# design.net
KiCad netlist of a schematic drawn in Altium Designer
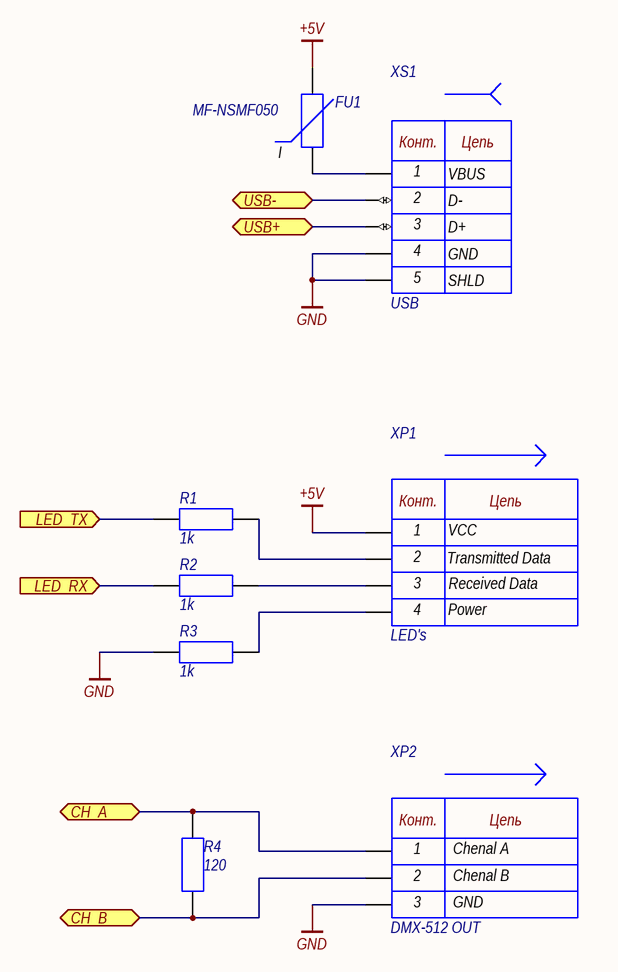
[diagram p0: Коммутация.SchDoc]

(export (version "E")
  (design (tool "Eeschema 10.0.6"))
  (components
    (comp (ref "FU1")
      (value "MF-NSMF050")
      (footprint "Components:F1206 Style1")
      (description "13.2V 0.5A")
      (fields (field (name "Comment") "MF-NSMF050_V"))
      (libsource (lib "Предохранители") (part "MF-NSMF050_V"))
    )
    (comp (ref "R1")
      (value "1k")
      (footprint "Components:R1206")
      (fields (field (name "Comment") "Res 1k"))
      (libsource (lib "") (part "Res 1k_1"))
    )
    (comp (ref "R2")
      (value "1k")
      (footprint "Components:R1206")
      (fields (field (name "Comment") "Res 1k"))
      (libsource (lib "") (part "Res 1k_1"))
    )
    (comp (ref "R3")
      (value "1k")
      (footprint "Components:R1206")
      (fields (field (name "Comment") "Res 1k"))
      (libsource (lib "Резисторы") (part "Res 1k"))
    )
    (comp (ref "R4")
      (value "120")
      (footprint "Components:R1206")
      (fields (field (name "Comment") "Res 120"))
      (libsource (lib "Резисторы") (part "Res 120"))
    )
    (comp (ref "XP1")
      (value "LED's")
      (footprint "Components:WF-4 (DS1070-4M)")
      (description "Power Con (DS1070-4M)")
      (fields (field (name "Comment") "WF-4"))
      (libsource (lib "Разъемы") (part "WF-4"))
    )
    (comp (ref "XP2")
      (value "DMX-512 OUT")
      (footprint "Components:WF-3")
      (description "Power Con (DS1070-4M)")
      (fields (field (name "Comment") "WF-3"))
      (libsource (lib "Разъемы") (part "WF-3"))
    )
    (comp (ref "XS1")
      (value "USB")
      (footprint "Components:USB-B")
      (description "Female B")
      (fields (field (name "Comment") "USB B"))
      (libsource (lib "Разъемы") (part "USB B"))
    )
  )
  (nets
    (net (code "1") (name "+5V") (class "Default")
      (node (ref "FU1") (pin "2") (pinfunction "2_2") (pintype "passive"))
      (node (ref "XP1") (pin "1") (pinfunction "1_1") (pintype "passive"))
    )
    (net (code "2") (name "/CH_A") (class "Default")
      (node (ref "R4") (pin "2") (pinfunction "2_2") (pintype "passive"))
      (node (ref "XP2") (pin "1") (pinfunction "1_1") (pintype "passive"))
    )
    (net (code "3") (name "/CH_B") (class "Default")
      (node (ref "R4") (pin "1") (pinfunction "1_1") (pintype "passive"))
      (node (ref "XP2") (pin "2") (pinfunction "2_2") (pintype "passive"))
    )
    (net (code "4") (name "/LED_RX") (class "Default")
      (node (ref "R2") (pin "1") (pinfunction "1_1") (pintype "passive"))
    )
    (net (code "5") (name "/LED_TX") (class "Default")
      (node (ref "R1") (pin "1") (pinfunction "1_1") (pintype "passive"))
    )
    (net (code "6") (name "/USB+") (class "Default")
      (node (ref "XS1") (pin "3") (pinfunction "D+_3") (pintype "bidirectional"))
    )
    (net (code "7") (name "/USB-") (class "Default")
      (node (ref "XS1") (pin "2") (pinfunction "D-_2") (pintype "bidirectional"))
    )
    (net (code "8") (name "GND") (class "Default")
      (node (ref "R3") (pin "1") (pinfunction "1_1") (pintype "passive"))
      (node (ref "XP2") (pin "3") (pinfunction "3_3") (pintype "passive"))
      (node (ref "XS1") (pin "4") (pinfunction "GND_4") (pintype "power_in"))
      (node (ref "XS1") (pin "MH1") (pinfunction "SHLD_MH1") (pintype "power_in"))
    )
    (net (code "9") (name "Net-(R1-Pad2)") (class "Default")
      (node (ref "R1") (pin "2") (pinfunction "2_2") (pintype "passive"))
      (node (ref "XP1") (pin "2") (pinfunction "2_2") (pintype "passive"))
    )
    (net (code "10") (name "Net-(R2-Pad2)") (class "Default")
      (node (ref "R2") (pin "2") (pinfunction "2_2") (pintype "passive"))
      (node (ref "XP1") (pin "3") (pinfunction "3_3") (pintype "passive"))
    )
    (net (code "11") (name "Net-(R3-Pad2)") (class "Default")
      (node (ref "R3") (pin "2") (pinfunction "2_2") (pintype "passive"))
      (node (ref "XP1") (pin "4") (pinfunction "4_4") (pintype "passive"))
    )
    (net (code "12") (name "Net-(XS1-VBUS)") (class "Default")
      (node (ref "FU1") (pin "1") (pinfunction "1_1") (pintype "passive"))
      (node (ref "XS1") (pin "1") (pinfunction "VBUS_1") (pintype "power_in"))
    )
  )
)
